# accelerometer.net
KiCad netlist of a schematic drawn in EAGLE
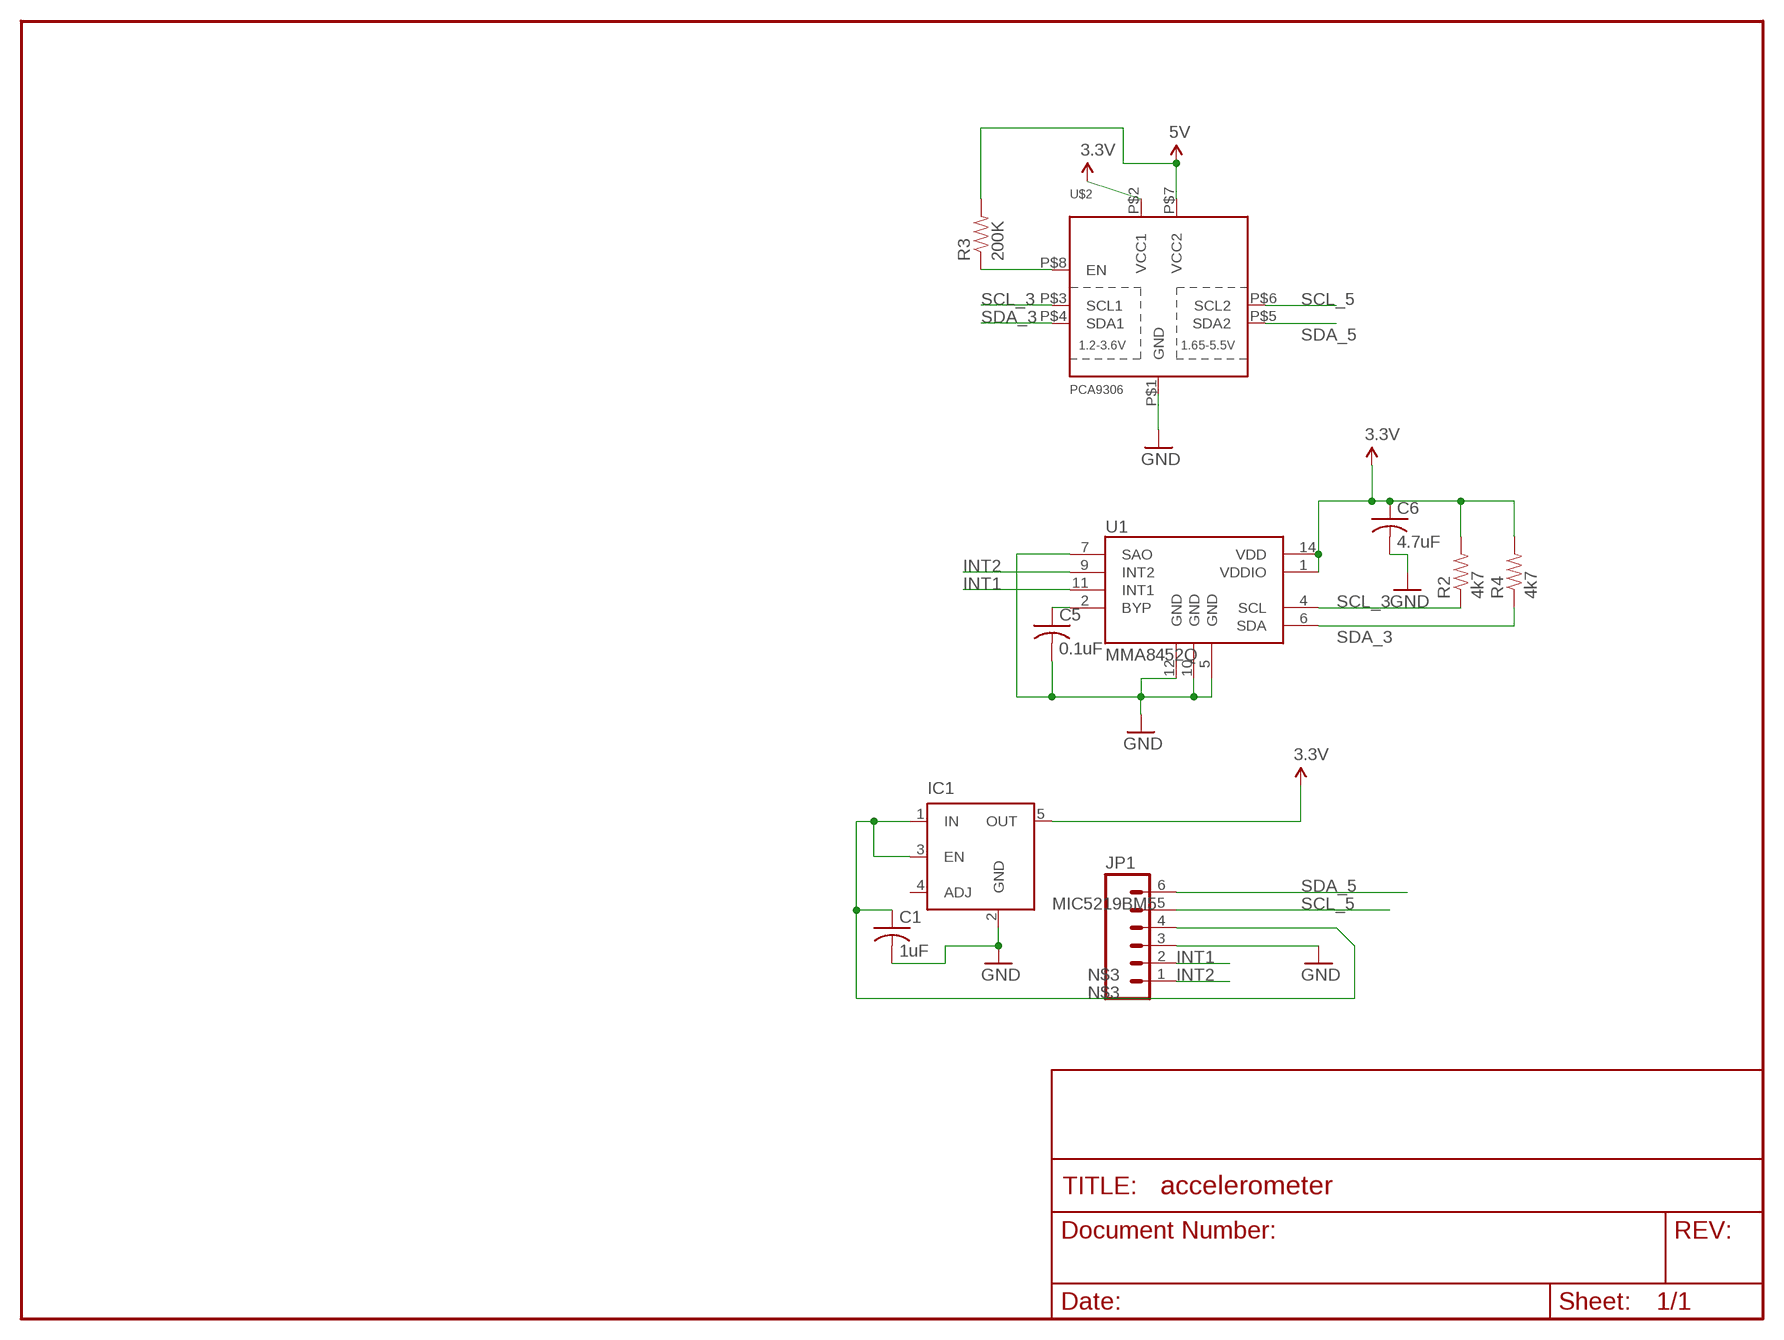
[diagram p0: schematic, sheet 1]

(export (version "E")
  (design (tool "Eeschema 10.0.6"))
  (components
    (comp (ref "C1")
      (value "1uF")
      (footprint "eagle-import:C0603K")
      (libsource (lib "eagle-import") (part "C-USC0603K"))
    )
    (comp (ref "C5")
      (value "0.1uF")
      (footprint "eagle-import:C0603K")
      (libsource (lib "eagle-import") (part "C-USC0603K"))
    )
    (comp (ref "C6")
      (value "4.7uF")
      (footprint "eagle-import:C0603K")
      (libsource (lib "eagle-import") (part "C-USC0603K"))
    )
    (comp (ref "IC1")
      (value "MIC5219BM5")
      (footprint "eagle-import:SOT23-5")
      (fields (field (name "MF") "ALTERA CORPORATION") (field (name "MPN") "MIC5219BM5 TR"))
      (libsource (lib "eagle-import") (part "MIC5219BM5"))
    )
    (comp (ref "JP1")
      (value "M06LOCK")
      (footprint "eagle-import:1X06_LOCK")
      (libsource (lib "eagle-import") (part "M06LOCK"))
    )
    (comp (ref "R2")
      (value "4k7")
      (footprint "eagle-import:0603-RES")
      (libsource (lib "eagle-import") (part "RESISTOR0603-RES"))
    )
    (comp (ref "R3")
      (value "200K")
      (footprint "eagle-import:0603-RES")
      (libsource (lib "eagle-import") (part "RESISTOR0603-RES"))
    )
    (comp (ref "R4")
      (value "4k7")
      (footprint "eagle-import:0603-RES")
      (libsource (lib "eagle-import") (part "RESISTOR0603-RES"))
    )
    (comp (ref "U$2")
      (value "PCA9306")
      (footprint "eagle-import:VSSOP-8")
      (libsource (lib "eagle-import") (part "PCA9306"))
    )
    (comp (ref "U1")
      (value "MMA8452Q")
      (footprint "eagle-import:QFN-16(5X3)")
      (libsource (lib "eagle-import") (part "MMA8452Q"))
    )
  )
  (nets
    (net (code "1") (name "/INT1") (class "Default")
      (node (ref "JP1") (pin "2") (pinfunction "2_2") (pintype "passive"))
      (node (ref "U1") (pin "11") (pinfunction "INT1_11") (pintype "bidirectional"))
    )
    (net (code "2") (name "/INT2") (class "Default")
      (node (ref "JP1") (pin "1") (pinfunction "1_1") (pintype "passive"))
      (node (ref "U1") (pin "9") (pinfunction "INT2_9") (pintype "bidirectional"))
    )
    (net (code "3") (name "/N$3") (class "Default")
      (node (ref "C1") (pin "1") (pinfunction "1_1") (pintype "passive"))
      (node (ref "IC1") (pin "1") (pinfunction "IN_1") (pintype "input"))
      (node (ref "IC1") (pin "3") (pinfunction "EN_3") (pintype "input"))
      (node (ref "JP1") (pin "4") (pinfunction "4_4") (pintype "passive"))
    )
    (net (code "4") (name "/SCL_3") (class "Default")
      (node (ref "R2") (pin "1") (pinfunction "1_1") (pintype "passive"))
      (node (ref "U$2") (pin "P$3") (pinfunction "SCL1_P$3") (pintype "bidirectional"))
      (node (ref "U1") (pin "4") (pinfunction "SCL_4") (pintype "bidirectional"))
    )
    (net (code "5") (name "/SCL_5") (class "Default")
      (node (ref "JP1") (pin "5") (pinfunction "5_5") (pintype "passive"))
      (node (ref "U$2") (pin "P$6") (pinfunction "SCL2_P$6") (pintype "bidirectional"))
    )
    (net (code "6") (name "/SDA_3") (class "Default")
      (node (ref "R4") (pin "1") (pinfunction "1_1") (pintype "passive"))
      (node (ref "U$2") (pin "P$4") (pinfunction "SDA1_P$4") (pintype "bidirectional"))
      (node (ref "U1") (pin "6") (pinfunction "SDA_6") (pintype "bidirectional"))
    )
    (net (code "7") (name "/SDA_5") (class "Default")
      (node (ref "JP1") (pin "6") (pinfunction "6_6") (pintype "passive"))
      (node (ref "U$2") (pin "P$5") (pinfunction "SDA2_P$5") (pintype "bidirectional"))
    )
    (net (code "8") (name "3.3V") (class "Default")
      (node (ref "C6") (pin "1") (pinfunction "1_1") (pintype "passive"))
      (node (ref "IC1") (pin "5") (pinfunction "OUT_5") (pintype "output"))
      (node (ref "R2") (pin "2") (pinfunction "2_2") (pintype "passive"))
      (node (ref "R4") (pin "2") (pinfunction "2_2") (pintype "passive"))
      (node (ref "U$2") (pin "P$2") (pinfunction "VCC1_P$2") (pintype "bidirectional"))
      (node (ref "U1") (pin "1") (pinfunction "VDDIO_1") (pintype "bidirectional"))
      (node (ref "U1") (pin "14") (pinfunction "VDD_14") (pintype "bidirectional"))
    )
    (net (code "9") (name "5V") (class "Default")
      (node (ref "R3") (pin "2") (pinfunction "2_2") (pintype "passive"))
      (node (ref "U$2") (pin "P$7") (pinfunction "VCC2_P$7") (pintype "bidirectional"))
    )
    (net (code "10") (name "GND") (class "Default")
      (node (ref "C1") (pin "2") (pinfunction "2_2") (pintype "passive"))
      (node (ref "C5") (pin "2") (pinfunction "2_2") (pintype "passive"))
      (node (ref "C6") (pin "2") (pinfunction "2_2") (pintype "passive"))
      (node (ref "IC1") (pin "2") (pinfunction "GND_2") (pintype "power_in"))
      (node (ref "JP1") (pin "3") (pinfunction "3_3") (pintype "passive"))
      (node (ref "U$2") (pin "P$1") (pinfunction "GND_P$1") (pintype "bidirectional"))
      (node (ref "U1") (pin "10") (pinfunction "GND_10") (pintype "bidirectional"))
      (node (ref "U1") (pin "12") (pinfunction "GND_12") (pintype "bidirectional"))
      (node (ref "U1") (pin "5") (pinfunction "GND_5") (pintype "bidirectional"))
      (node (ref "U1") (pin "7") (pinfunction "SAO_7") (pintype "bidirectional"))
    )
    (net (code "11") (name "Net-(U$2-EN)") (class "Default")
      (node (ref "R3") (pin "1") (pinfunction "1_1") (pintype "passive"))
      (node (ref "U$2") (pin "P$8") (pinfunction "EN_P$8") (pintype "bidirectional"))
    )
    (net (code "12") (name "Net-(U1-BYP)") (class "Default")
      (node (ref "C5") (pin "1") (pinfunction "1_1") (pintype "passive"))
      (node (ref "U1") (pin "2") (pinfunction "BYP_2") (pintype "bidirectional"))
    )
    (net (code "13") (name "unconnected-(IC1-ADJ-Pad4)") (class "Default")
      (node (ref "IC1") (pin "4") (pinfunction "ADJ_4") (pintype "passive"))
    )
  )
)
